# P05_MPU4.net
KiCad netlist of a schematic drawn in Altium Designer
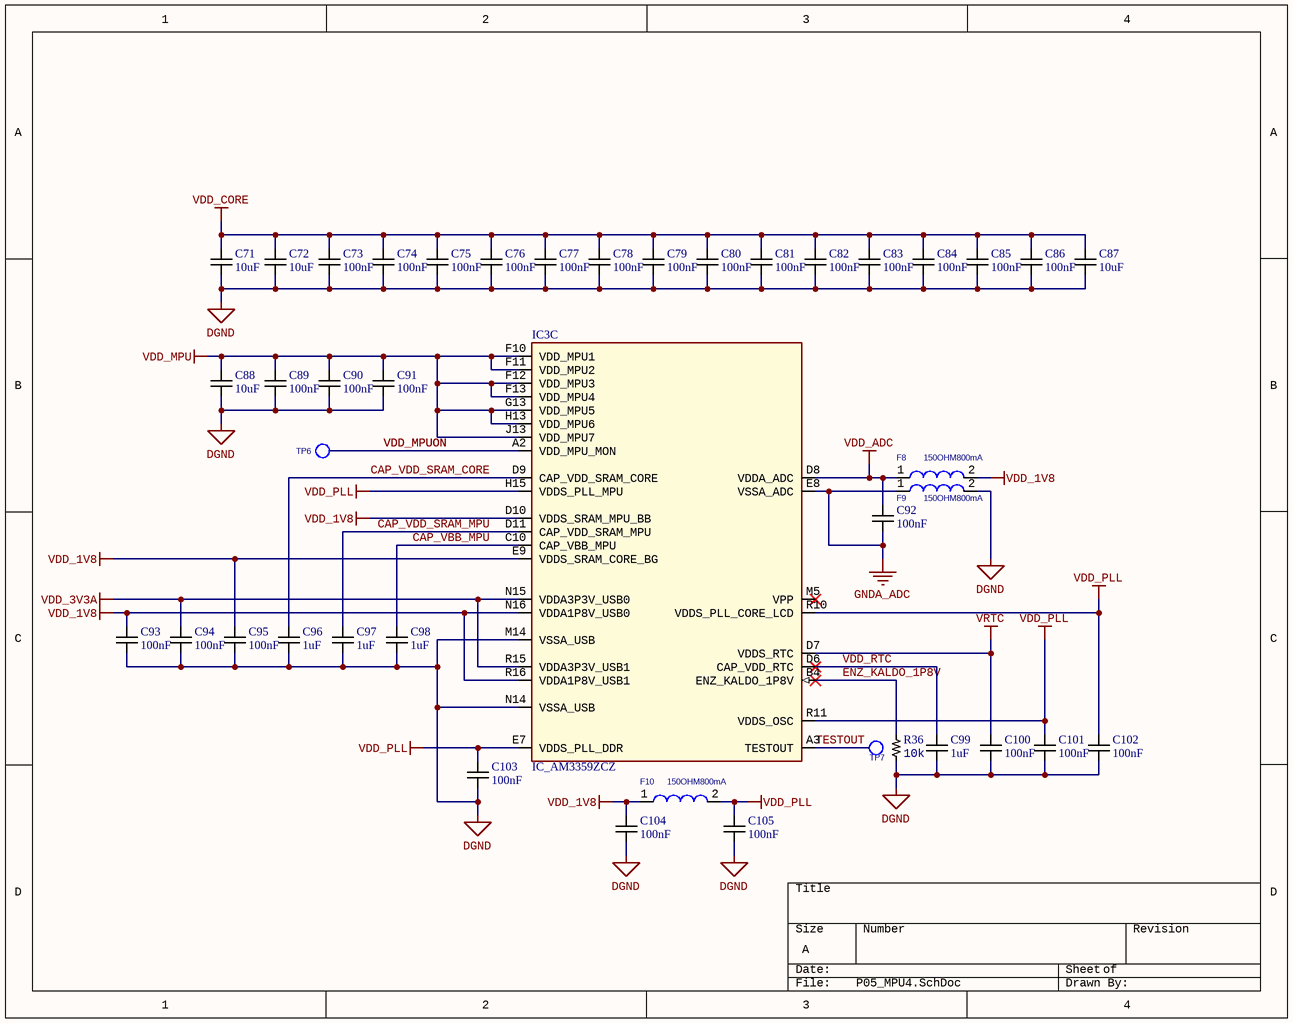
[diagram p0: P05_MPU4.SchDoc]

(export (version "E")
  (design (tool "Eeschema 10.0.6"))
  (components
    (comp (ref "C71")
      (value "C2012X6S1A106K085AC")
      (footprint "Orient:CAP0805")
      (description "MLCC 10uF 0805 SMD")
      (fields
        (field (name "MANUFACTURER") "TDK")
        (field (name "CAPACITANCE") "10uF")
        (field (name "TOLERANCE") "10%")
      )
      (libsource (lib "Orient") (part "CAP_10uF"))
    )
    (comp (ref "C72")
      (value "C2012X6S1A106K085AC")
      (footprint "Orient:CAP0805")
      (description "MLCC 10uF 0805 SMD")
      (fields
        (field (name "CAPACITANCE") "10uF")
        (field (name "MANUFACTURER") "TDK")
        (field (name "TOLERANCE") "10%")
      )
      (libsource (lib "Orient") (part "CAP_10uF"))
    )
    (comp (ref "C73")
      (value "C0402C104K4RACTU")
      (footprint "Orient:CAP0402")
      (description "MLCC 100nF 0402 SMD")
      (fields
        (field (name "MANUFACTURER") "KEMET")
        (field (name "CAPACITANCE") "100nF")
        (field (name "TOLERANCE") "10%")
      )
      (libsource (lib "Orient") (part "CAP_100nF"))
    )
    (comp (ref "C74")
      (value "C0402C104K4RACTU")
      (footprint "Orient:CAP0402")
      (description "MLCC 100nF 0402 SMD")
      (fields
        (field (name "MANUFACTURER") "KEMET")
        (field (name "CAPACITANCE") "100nF")
        (field (name "TOLERANCE") "10%")
      )
      (libsource (lib "Orient") (part "CAP_100nF"))
    )
    (comp (ref "C75")
      (value "C0402C104K4RACTU")
      (footprint "Orient:CAP0402")
      (description "MLCC 100nF 0402 SMD")
      (fields
        (field (name "MANUFACTURER") "KEMET")
        (field (name "CAPACITANCE") "100nF")
        (field (name "TOLERANCE") "10%")
      )
      (libsource (lib "Orient") (part "CAP_100nF"))
    )
    (comp (ref "C76")
      (value "C0402C104K4RACTU")
      (footprint "Orient:CAP0402")
      (description "MLCC 100nF 0402 SMD")
      (fields
        (field (name "MANUFACTURER") "KEMET")
        (field (name "CAPACITANCE") "100nF")
        (field (name "TOLERANCE") "10%")
      )
      (libsource (lib "Orient") (part "CAP_100nF"))
    )
    (comp (ref "C77")
      (value "C0402C104K4RACTU")
      (footprint "Orient:CAP0402")
      (description "MLCC 100nF 0402 SMD")
      (fields
        (field (name "MANUFACTURER") "KEMET")
        (field (name "CAPACITANCE") "100nF")
        (field (name "TOLERANCE") "10%")
      )
      (libsource (lib "Orient") (part "CAP_100nF"))
    )
    (comp (ref "C78")
      (value "C0402C104K4RACTU")
      (footprint "Orient:CAP0402")
      (description "MLCC 100nF 0402 SMD")
      (fields
        (field (name "MANUFACTURER") "KEMET")
        (field (name "CAPACITANCE") "100nF")
        (field (name "TOLERANCE") "10%")
      )
      (libsource (lib "Orient") (part "CAP_100nF"))
    )
    (comp (ref "C79")
      (value "C0402C104K4RACTU")
      (footprint "Orient:CAP0402")
      (description "MLCC 100nF 0402 SMD")
      (fields
        (field (name "MANUFACTURER") "KEMET")
        (field (name "CAPACITANCE") "100nF")
        (field (name "TOLERANCE") "10%")
      )
      (libsource (lib "Orient") (part "CAP_100nF"))
    )
    (comp (ref "C80")
      (value "C0402C104K4RACTU")
      (footprint "Orient:CAP0402")
      (description "MLCC 100nF 0402 SMD")
      (fields
        (field (name "MANUFACTURER") "KEMET")
        (field (name "CAPACITANCE") "100nF")
        (field (name "TOLERANCE") "10%")
      )
      (libsource (lib "Orient") (part "CAP_100nF"))
    )
    (comp (ref "C81")
      (value "C0402C104K4RACTU")
      (footprint "Orient:CAP0402")
      (description "MLCC 100nF 0402 SMD")
      (fields
        (field (name "MANUFACTURER") "KEMET")
        (field (name "CAPACITANCE") "100nF")
        (field (name "TOLERANCE") "10%")
      )
      (libsource (lib "Orient") (part "CAP_100nF"))
    )
    (comp (ref "C82")
      (value "C0402C104K4RACTU")
      (footprint "Orient:CAP0402")
      (description "MLCC 100nF 0402 SMD")
      (fields
        (field (name "MANUFACTURER") "KEMET")
        (field (name "CAPACITANCE") "100nF")
        (field (name "TOLERANCE") "10%")
      )
      (libsource (lib "Orient") (part "CAP_100nF"))
    )
    (comp (ref "C83")
      (value "C0402C104K4RACTU")
      (footprint "Orient:CAP0402")
      (description "MLCC 100nF 0402 SMD")
      (fields
        (field (name "MANUFACTURER") "KEMET")
        (field (name "CAPACITANCE") "100nF")
        (field (name "TOLERANCE") "10%")
      )
      (libsource (lib "Orient") (part "CAP_100nF"))
    )
    (comp (ref "C84")
      (value "C0402C104K4RACTU")
      (footprint "Orient:CAP0402")
      (description "MLCC 100nF 0402 SMD")
      (fields
        (field (name "MANUFACTURER") "KEMET")
        (field (name "CAPACITANCE") "100nF")
        (field (name "TOLERANCE") "10%")
      )
      (libsource (lib "Orient") (part "CAP_100nF"))
    )
    (comp (ref "C85")
      (value "C0402C104K4RACTU")
      (footprint "Orient:CAP0402")
      (description "MLCC 100nF 0402 SMD")
      (fields
        (field (name "MANUFACTURER") "KEMET")
        (field (name "CAPACITANCE") "100nF")
        (field (name "TOLERANCE") "10%")
      )
      (libsource (lib "Orient") (part "CAP_100nF"))
    )
    (comp (ref "C86")
      (value "C0402C104K4RACTU")
      (footprint "Orient:CAP0402")
      (description "MLCC 100nF 0402 SMD")
      (fields
        (field (name "MANUFACTURER") "KEMET")
        (field (name "CAPACITANCE") "100nF")
        (field (name "TOLERANCE") "10%")
      )
      (libsource (lib "Orient") (part "CAP_100nF"))
    )
    (comp (ref "C87")
      (value "C2012X6S1A106K085AC")
      (footprint "Orient:CAP0805")
      (description "MLCC 10uF 0805 SMD")
      (fields
        (field (name "MANUFACTURER") "TDK")
        (field (name "CAPACITANCE") "10uF")
        (field (name "TOLERANCE") "10%")
      )
      (libsource (lib "Orient") (part "CAP_10uF"))
    )
    (comp (ref "C88")
      (value "C2012X6S1A106K085AC")
      (footprint "Orient:CAP0805")
      (description "MLCC 10uF 0805 SMD")
      (fields
        (field (name "MANUFACTURER") "TDK")
        (field (name "CAPACITANCE") "10uF")
        (field (name "TOLERANCE") "10%")
      )
      (libsource (lib "Orient") (part "CAP_10uF"))
    )
    (comp (ref "C89")
      (value "C0402C104K4RACTU")
      (footprint "Orient:CAP0402")
      (description "MLCC 100nF 0402 SMD")
      (fields
        (field (name "MANUFACTURER") "KEMET")
        (field (name "CAPACITANCE") "100nF")
        (field (name "TOLERANCE") "10%")
      )
      (libsource (lib "Orient") (part "CAP_100nF"))
    )
    (comp (ref "C90")
      (value "C0402C104K4RACTU")
      (footprint "Orient:CAP0402")
      (description "MLCC 100nF 0402 SMD")
      (fields
        (field (name "MANUFACTURER") "KEMET")
        (field (name "CAPACITANCE") "100nF")
        (field (name "TOLERANCE") "10%")
      )
      (libsource (lib "Orient") (part "CAP_100nF"))
    )
    (comp (ref "C91")
      (value "C0402C104K4RACTU")
      (footprint "Orient:CAP0402")
      (description "MLCC 100nF 0402 SMD")
      (fields
        (field (name "MANUFACTURER") "KEMET")
        (field (name "CAPACITANCE") "100nF")
        (field (name "TOLERANCE") "10%")
      )
      (libsource (lib "Orient") (part "CAP_100nF"))
    )
    (comp (ref "C92")
      (value "C0402C104K4RACTU")
      (footprint "Orient:CAP0402")
      (description "MLCC 100nF 0402 SMD")
      (fields
        (field (name "MANUFACTURER") "KEMET")
        (field (name "CAPACITANCE") "100nF")
        (field (name "TOLERANCE") "10%")
      )
      (libsource (lib "Orient") (part "CAP_100nF"))
    )
    (comp (ref "C93")
      (value "C0402C104K4RACTU")
      (footprint "Orient:CAP0402")
      (description "MLCC 100nF 0402 SMD")
      (fields
        (field (name "MANUFACTURER") "KEMET")
        (field (name "CAPACITANCE") "100nF")
        (field (name "TOLERANCE") "10%")
      )
      (libsource (lib "Orient") (part "CAP_100nF"))
    )
    (comp (ref "C94")
      (value "C0402C104K4RACTU")
      (footprint "Orient:CAP0402")
      (description "MLCC 100nF 0402 SMD")
      (fields
        (field (name "MANUFACTURER") "KEMET")
        (field (name "CAPACITANCE") "100nF")
        (field (name "TOLERANCE") "10%")
      )
      (libsource (lib "Orient") (part "CAP_100nF"))
    )
    (comp (ref "C95")
      (value "C0402C104K4RACTU")
      (footprint "Orient:CAP0402")
      (description "MLCC 100nF 0402 SMD")
      (fields
        (field (name "MANUFACTURER") "KEMET")
        (field (name "CAPACITANCE") "100nF")
        (field (name "TOLERANCE") "10%")
      )
      (libsource (lib "Orient") (part "CAP_100nF"))
    )
    (comp (ref "C96")
      (value "CC0402KRX5R6BB105")
      (footprint "Orient:CAP0402")
      (description "MLCC 1uF 0402 SMD")
      (fields
        (field (name "MANUFACTURER") "Yageo")
        (field (name "CAPACITANCE") "1uF")
        (field (name "TOLERANCE") "10%")
      )
      (libsource (lib "Orient") (part "CAP_1uF"))
    )
    (comp (ref "C97")
      (value "CC0402KRX5R6BB105")
      (footprint "Orient:CAP0402")
      (description "MLCC 1uF 0402 SMD")
      (fields
        (field (name "MANUFACTURER") "Yageo")
        (field (name "CAPACITANCE") "1uF")
        (field (name "TOLERANCE") "10%")
      )
      (libsource (lib "Orient") (part "CAP_1uF"))
    )
    (comp (ref "C98")
      (value "CC0402KRX5R6BB105")
      (footprint "Orient:CAP0402")
      (description "MLCC 1uF 0402 SMD")
      (fields
        (field (name "MANUFACTURER") "Yageo")
        (field (name "CAPACITANCE") "1uF")
        (field (name "TOLERANCE") "10%")
      )
      (libsource (lib "Orient") (part "CAP_1uF"))
    )
    (comp (ref "C99")
      (value "CC0402KRX5R6BB105")
      (footprint "Orient:CAP0402")
      (description "MLCC 1uF 0402 SMD")
      (fields
        (field (name "MANUFACTURER") "Yageo")
        (field (name "CAPACITANCE") "1uF")
        (field (name "TOLERANCE") "10%")
      )
      (libsource (lib "Orient") (part "CAP_1uF"))
    )
    (comp (ref "C100")
      (value "C0402C104K4RACTU")
      (footprint "Orient:CAP0402")
      (description "MLCC 100nF 0402 SMD")
      (fields
        (field (name "MANUFACTURER") "KEMET")
        (field (name "CAPACITANCE") "100nF")
        (field (name "TOLERANCE") "10%")
      )
      (libsource (lib "Orient") (part "CAP_100nF"))
    )
    (comp (ref "C101")
      (value "C0402C104K4RACTU")
      (footprint "Orient:CAP0402")
      (description "MLCC 100nF 0402 SMD")
      (fields
        (field (name "MANUFACTURER") "KEMET")
        (field (name "CAPACITANCE") "100nF")
        (field (name "TOLERANCE") "10%")
      )
      (libsource (lib "Orient") (part "CAP_100nF"))
    )
    (comp (ref "C102")
      (value "C0402C104K4RACTU")
      (footprint "Orient:CAP0402")
      (description "MLCC 100nF 0402 SMD")
      (fields
        (field (name "MANUFACTURER") "KEMET")
        (field (name "CAPACITANCE") "100nF")
        (field (name "TOLERANCE") "10%")
      )
      (libsource (lib "Orient") (part "CAP_100nF"))
    )
    (comp (ref "C103")
      (value "C0402C104K4RACTU")
      (footprint "Orient:CAP0402")
      (description "MLCC 100nF 0402 SMD")
      (fields
        (field (name "MANUFACTURER") "KEMET")
        (field (name "CAPACITANCE") "100nF")
        (field (name "TOLERANCE") "10%")
      )
      (libsource (lib "Orient") (part "CAP_100nF"))
    )
    (comp (ref "C104")
      (value "C0402C104K4RACTU")
      (footprint "Orient:CAP0402")
      (description "MLCC 100nF 0402 SMD")
      (fields
        (field (name "MANUFACTURER") "KEMET")
        (field (name "CAPACITANCE") "100nF")
        (field (name "TOLERANCE") "10%")
      )
      (libsource (lib "Orient") (part "CAP_100nF"))
    )
    (comp (ref "C105")
      (value "C0402C104K4RACTU")
      (footprint "Orient:CAP0402")
      (description "MLCC 100nF 0402 SMD")
      (fields
        (field (name "MANUFACTURER") "KEMET")
        (field (name "CAPACITANCE") "100nF")
        (field (name "TOLERANCE") "10%")
      )
      (libsource (lib "Orient") (part "CAP_100nF"))
    )
    (comp (ref "F8")
      (value "150OHM800mA")
      (footprint "Orient:FB0805")
      (description "FERRITE 800MA 150 OHM 0805 SMD")
      (fields (field (name "MFR") "Steward") (field (name "TIINTPARTNUMBER") "1L0010"))
      (libsource (lib "Orient") (part "FERR"))
    )
    (comp (ref "F9")
      (value "150OHM800mA")
      (footprint "Orient:FB0805")
      (description "FERRITE 800MA 150 OHM 0805 SMD")
      (fields (field (name "MFR") "Steward") (field (name "TIINTPARTNUMBER") "1L0010"))
      (libsource (lib "Orient") (part "FERR"))
    )
    (comp (ref "F10")
      (value "150OHM800mA")
      (footprint "Orient:FB0805")
      (description "FERRITE 800MA 150 OHM 0805 SMD")
      (fields (field (name "MFR") "Steward") (field (name "TIINTPARTNUMBER") "1L0010"))
      (libsource (lib "Orient") (part "FERR"))
    )
    (comp (ref "IC3")
      (value "IC_AM3359ZCZ")
      (footprint "Orient:BGA-324")
      (description "SubArctic Cortex A8 Processor 18x18")
      (fields
        (field (name "MANUFACTURER") "Texas Instruments")
        (field (name "MANUFACTURER PART NUMBER") "XAM3359ZCZ")
      )
      (libsource (lib "Orient") (part "IC_AM335X_ZCE_1"))
    )
    (comp (ref "R36")
      (value "RC0402FR-0710KL")
      (footprint "Orient:RES0402")
      (description "Resistor 10kOhm 0402 SMD")
      (fields
        (field (name "MANUFACTURER") "Yageo")
        (field (name "TOLERANCE") "1%")
        (field (name "RESISTANCE") "10k")
      )
      (libsource (lib "Orient") (part "RES_10k"))
    )
    (comp (ref "TP6")
      (value "TESTPT1")
      (footprint "Orient:tp1-8040")
      (libsource (lib "Orient") (part "TESTPT1"))
    )
    (comp (ref "TP7")
      (value "TESTPT1")
      (footprint "Orient:tp1-8040")
      (libsource (lib "Orient") (part "TESTPT1"))
    )
  )
  (nets
    (net (code "1") (name "/CAP_VBB_MPU") (class "Default")
      (node (ref "C98") (pin "1") (pintype "passive"))
      (node (ref "IC3") (pin "C10") (pinfunction "CAP_VBB_MPU_C10") (pintype "passive"))
    )
    (net (code "2") (name "/CAP_VDD_SRAM_CORE") (class "Default")
      (node (ref "C96") (pin "1") (pintype "passive"))
      (node (ref "IC3") (pin "D9") (pinfunction "CAP_VDD_SRAM_CORE_D9") (pintype "power_in"))
    )
    (net (code "3") (name "/CAP_VDD_SRAM_MPU") (class "Default")
      (node (ref "C97") (pin "1") (pintype "passive"))
      (node (ref "IC3") (pin "D11") (pinfunction "CAP_VDD_SRAM_MPU_D11") (pintype "power_in"))
    )
    (net (code "4") (name "/ENZ_KALDO_1P8V") (class "Default")
      (node (ref "IC3") (pin "B4") (pinfunction "ENZ_KALDO_1P8V_B4") (pintype "input"))
      (node (ref "R36") (pin "1") (pintype "passive"))
    )
    (net (code "5") (name "/TESTOUT") (class "Default")
      (node (ref "IC3") (pin "A3") (pinfunction "TESTOUT_A3") (pintype "passive"))
      (node (ref "TP7") (pin "1") (pinfunction "TP_1") (pintype "passive"))
    )
    (net (code "6") (name "/VDD_MPUON") (class "Default")
      (node (ref "IC3") (pin "A2") (pinfunction "VDD_MPU_MON_A2") (pintype "passive"))
      (node (ref "TP6") (pin "1") (pinfunction "TP_1") (pintype "passive"))
    )
    (net (code "7") (name "/VDD_RTC") (class "Default")
      (node (ref "C99") (pin "1") (pintype "passive"))
      (node (ref "IC3") (pin "D6") (pinfunction "CAP_VDD_RTC_D6") (pintype "power_in"))
    )
    (net (code "8") (name "DGND") (class "Default")
      (node (ref "C100") (pin "2") (pintype "passive"))
      (node (ref "C101") (pin "2") (pintype "passive"))
      (node (ref "C102") (pin "2") (pintype "passive"))
      (node (ref "C103") (pin "2") (pintype "passive"))
      (node (ref "C104") (pin "2") (pintype "passive"))
      (node (ref "C105") (pin "2") (pintype "passive"))
      (node (ref "C71") (pin "1") (pintype "passive"))
      (node (ref "C72") (pin "1") (pintype "passive"))
      (node (ref "C73") (pin "2") (pintype "passive"))
      (node (ref "C74") (pin "2") (pintype "passive"))
      (node (ref "C75") (pin "2") (pintype "passive"))
      (node (ref "C76") (pin "2") (pintype "passive"))
      (node (ref "C77") (pin "2") (pintype "passive"))
      (node (ref "C78") (pin "2") (pintype "passive"))
      (node (ref "C79") (pin "2") (pintype "passive"))
      (node (ref "C80") (pin "2") (pintype "passive"))
      (node (ref "C81") (pin "2") (pintype "passive"))
      (node (ref "C82") (pin "2") (pintype "passive"))
      (node (ref "C83") (pin "2") (pintype "passive"))
      (node (ref "C84") (pin "2") (pintype "passive"))
      (node (ref "C85") (pin "2") (pintype "passive"))
      (node (ref "C86") (pin "2") (pintype "passive"))
      (node (ref "C87") (pin "1") (pintype "passive"))
      (node (ref "C88") (pin "1") (pintype "passive"))
      (node (ref "C89") (pin "2") (pintype "passive"))
      (node (ref "C90") (pin "2") (pintype "passive"))
      (node (ref "C91") (pin "2") (pintype "passive"))
      (node (ref "C93") (pin "2") (pintype "passive"))
      (node (ref "C94") (pin "2") (pintype "passive"))
      (node (ref "C95") (pin "2") (pintype "passive"))
      (node (ref "C96") (pin "2") (pintype "passive"))
      (node (ref "C97") (pin "2") (pintype "passive"))
      (node (ref "C98") (pin "2") (pintype "passive"))
      (node (ref "C99") (pin "2") (pintype "passive"))
      (node (ref "F9") (pin "2") (pinfunction "2_2") (pintype "passive"))
      (node (ref "IC3") (pin "M14") (pinfunction "VSSA_USB_M14") (pintype "power_in"))
      (node (ref "IC3") (pin "N14") (pinfunction "VSSA_USB_N14") (pintype "power_in"))
      (node (ref "R36") (pin "2") (pintype "passive"))
    )
    (net (code "9") (name "GNDA_ADC") (class "Default")
      (node (ref "C92") (pin "2") (pintype "passive"))
      (node (ref "F9") (pin "1") (pinfunction "1_1") (pintype "passive"))
      (node (ref "IC3") (pin "E8") (pinfunction "VSSA_ADC_E8") (pintype "power_in"))
    )
    (net (code "10") (name "VDD_1V8") (class "Default")
      (node (ref "C104") (pin "1") (pintype "passive"))
      (node (ref "C93") (pin "1") (pintype "passive"))
      (node (ref "C95") (pin "1") (pintype "passive"))
      (node (ref "F10") (pin "1") (pinfunction "1_1") (pintype "passive"))
      (node (ref "F8") (pin "2") (pinfunction "2_2") (pintype "passive"))
      (node (ref "IC3") (pin "D10") (pinfunction "VDDS_SRAM_MPU_BB_D10") (pintype "power_in"))
      (node (ref "IC3") (pin "E9") (pinfunction "VDDS_SRAM_CORE_BG_E9") (pintype "power_in"))
      (node (ref "IC3") (pin "N16") (pinfunction "VDDA1P8V_USB0_N16") (pintype "power_in"))
      (node (ref "IC3") (pin "R16") (pinfunction "VDDA1P8V_USB1_R16") (pintype "power_in"))
    )
    (net (code "11") (name "VDD_3V3A") (class "Default")
      (node (ref "C94") (pin "1") (pintype "passive"))
      (node (ref "IC3") (pin "N15") (pinfunction "VDDA3P3V_USB0_N15") (pintype "power_in"))
      (node (ref "IC3") (pin "R15") (pinfunction "VDDA3P3V_USB1_R15") (pintype "power_in"))
    )
    (net (code "12") (name "VDD_ADC") (class "Default")
      (node (ref "C92") (pin "1") (pintype "passive"))
      (node (ref "F8") (pin "1") (pinfunction "1_1") (pintype "passive"))
      (node (ref "IC3") (pin "D8") (pinfunction "VDDA_ADC_D8") (pintype "power_in"))
    )
    (net (code "13") (name "VDD_CORE") (class "Default")
      (node (ref "C71") (pin "2") (pintype "passive"))
      (node (ref "C72") (pin "2") (pintype "passive"))
      (node (ref "C73") (pin "1") (pintype "passive"))
      (node (ref "C74") (pin "1") (pintype "passive"))
      (node (ref "C75") (pin "1") (pintype "passive"))
      (node (ref "C76") (pin "1") (pintype "passive"))
      (node (ref "C77") (pin "1") (pintype "passive"))
      (node (ref "C78") (pin "1") (pintype "passive"))
      (node (ref "C79") (pin "1") (pintype "passive"))
      (node (ref "C80") (pin "1") (pintype "passive"))
      (node (ref "C81") (pin "1") (pintype "passive"))
      (node (ref "C82") (pin "1") (pintype "passive"))
      (node (ref "C83") (pin "1") (pintype "passive"))
      (node (ref "C84") (pin "1") (pintype "passive"))
      (node (ref "C85") (pin "1") (pintype "passive"))
      (node (ref "C86") (pin "1") (pintype "passive"))
      (node (ref "C87") (pin "2") (pintype "passive"))
    )
    (net (code "14") (name "VDD_MPU") (class "Default")
      (node (ref "C88") (pin "2") (pintype "passive"))
      (node (ref "C89") (pin "1") (pintype "passive"))
      (node (ref "C90") (pin "1") (pintype "passive"))
      (node (ref "C91") (pin "1") (pintype "passive"))
      (node (ref "IC3") (pin "F10") (pinfunction "VDD_MPU1_F10") (pintype "power_in"))
      (node (ref "IC3") (pin "F11") (pinfunction "VDD_MPU2_F11") (pintype "power_in"))
      (node (ref "IC3") (pin "F12") (pinfunction "VDD_MPU3_F12") (pintype "power_in"))
      (node (ref "IC3") (pin "F13") (pinfunction "VDD_MPU4_F13") (pintype "power_in"))
      (node (ref "IC3") (pin "G13") (pinfunction "VDD_MPU5_G13") (pintype "power_in"))
      (node (ref "IC3") (pin "H13") (pinfunction "VDD_MPU6_H13") (pintype "power_in"))
      (node (ref "IC3") (pin "J13") (pinfunction "VDD_MPU7_J13") (pintype "power_in"))
    )
    (net (code "15") (name "VDD_PLL") (class "Default")
      (node (ref "C101") (pin "1") (pintype "passive"))
      (node (ref "C102") (pin "1") (pintype "passive"))
      (node (ref "C103") (pin "1") (pintype "passive"))
      (node (ref "C105") (pin "1") (pintype "passive"))
      (node (ref "F10") (pin "2") (pinfunction "2_2") (pintype "passive"))
      (node (ref "IC3") (pin "E7") (pinfunction "VDDS_PLL_DDR_E7") (pintype "power_in"))
      (node (ref "IC3") (pin "H15") (pinfunction "VDDS_PLL_MPU_H15") (pintype "power_in"))
      (node (ref "IC3") (pin "R10") (pinfunction "VDDS_PLL_CORE_LCD_R10") (pintype "power_in"))
      (node (ref "IC3") (pin "R11") (pinfunction "VDDS_OSC_R11") (pintype "power_in"))
    )
    (net (code "16") (name "VRTC") (class "Default")
      (node (ref "C100") (pin "1") (pintype "passive"))
      (node (ref "IC3") (pin "D7") (pinfunction "VDDS_RTC_D7") (pintype "power_in"))
    )
    (net (code "17") (name "unconnected-(IC3C-VPP-PadM5)") (class "Default")
      (node (ref "IC3") (pin "M5") (pinfunction "VPP_M5") (pintype "power_in+no_connect"))
    )
  )
)
